# Sheet1.net
KiCad netlist of a schematic drawn in Altium Designer
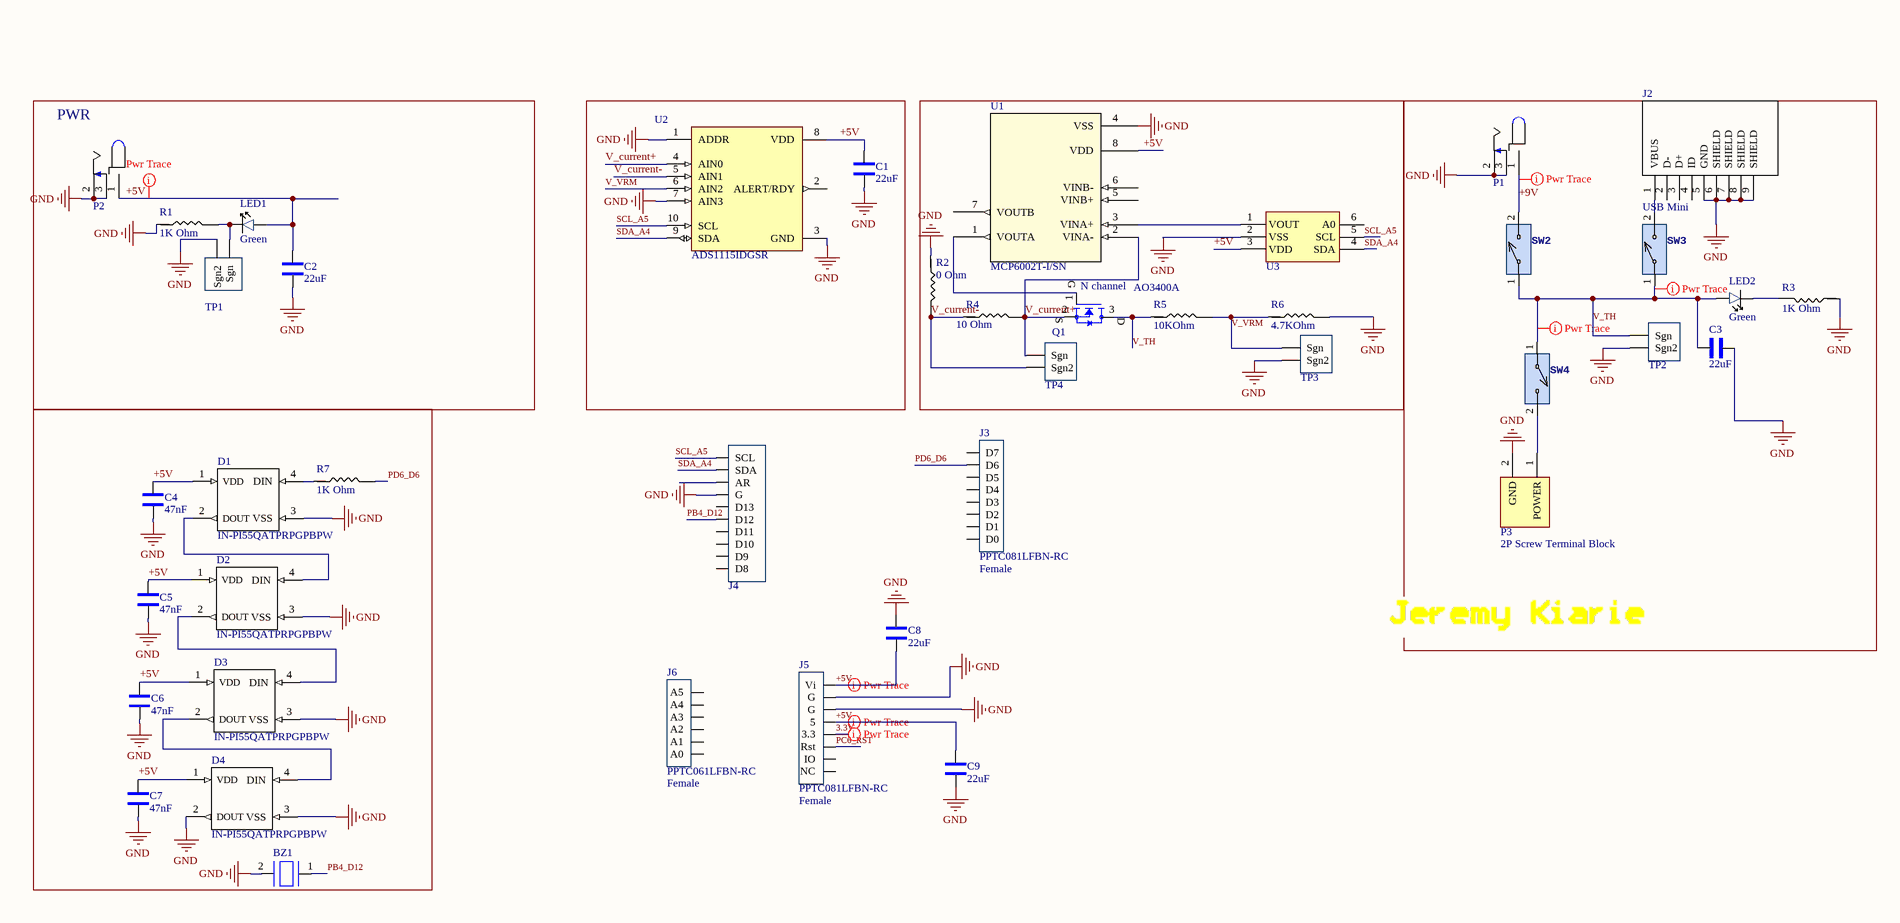
[diagram p0: Sheet1.SchDoc, left]
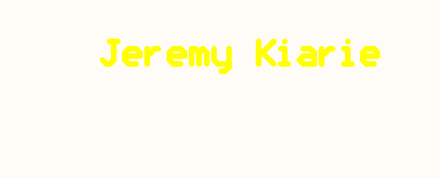
[diagram p1: Sheet1.SchDoc, right]

(export (version "E")
  (design (tool "Eeschema 10.0.6"))
  (components
    (comp (ref "BZ1")
      (value "AT-1224-TWT-5V-2-R")
      (footprint "BUZZER- TH")
      (libsource (lib "ECEN5730Lib_2023_05_DS") (part "BUZZER_1"))
    )
    (comp (ref "C1")
      (value "22uF")
      (footprint "1206_Passive_Capacitor")
      (description "22uF ±10% 25V X5R 1206 Multilayer Ceramic Capacitors MLCC - SMD/SMT RoHS")
      (fields (field (name "MFR PART #") "CL31A226KAHNNNE") (field (name "LCSC PART#") "C12891"))
      (libsource (lib "ECEN5730Lib_2023_05_DS") (part "C_22uF_1206"))
    )
    (comp (ref "C2")
      (value "22uF")
      (footprint "1206_Passive_Capacitor")
      (description "22uF ±10% 25V X5R 1206 Multilayer Ceramic Capacitors MLCC - SMD/SMT RoHS")
      (fields (field (name "MFR PART #") "CL31A226KAHNNNE") (field (name "LCSC PART#") "C12891"))
      (libsource (lib "ECEN5730Lib_2023_05_DS") (part "C_22uF_1206"))
    )
    (comp (ref "C3")
      (value "22uF")
      (footprint "1206_Passive_Capacitor")
      (description "22uF ±10% 25V X5R 1206 Multilayer Ceramic Capacitors MLCC - SMD/SMT RoHS")
      (fields (field (name "MFR PART #") "CL31A226KAHNNNE") (field (name "LCSC PART#") "C12891"))
      (libsource (lib "ECEN5730Lib_2023_05_DS") (part "C_22uF_1206"))
    )
    (comp (ref "C4")
      (value "47nF")
      (footprint "1206_Passive_Capacitor")
      (description "47nF ±5% 50V C0G 1206 Multilayer Ceramic Capacitors MLCC - SMD/SMT RoHS")
      (fields (field (name "LCSC PART#") "C21812") (field (name "MFR PART #") "GRM31M5C1H473JA01L"))
      (libsource (lib "ECEN5730Lib_2023_05_DS") (part "C_47nF_1206"))
    )
    (comp (ref "C5")
      (value "47nF")
      (footprint "1206_Passive_Capacitor")
      (description "47nF ±5% 50V C0G 1206 Multilayer Ceramic Capacitors MLCC - SMD/SMT RoHS")
      (fields (field (name "LCSC PART#") "C21812") (field (name "MFR PART #") "GRM31M5C1H473JA01L"))
      (libsource (lib "ECEN5730Lib_2023_05_DS") (part "C_47nF_1206"))
    )
    (comp (ref "C6")
      (value "47nF")
      (footprint "1206_Passive_Capacitor")
      (description "47nF ±5% 50V C0G 1206 Multilayer Ceramic Capacitors MLCC - SMD/SMT RoHS")
      (fields (field (name "LCSC PART#") "C21812") (field (name "MFR PART #") "GRM31M5C1H473JA01L"))
      (libsource (lib "ECEN5730Lib_2023_05_DS") (part "C_47nF_1206"))
    )
    (comp (ref "C7")
      (value "47nF")
      (footprint "1206_Passive_Capacitor")
      (description "47nF ±5% 50V C0G 1206 Multilayer Ceramic Capacitors MLCC - SMD/SMT RoHS")
      (fields (field (name "LCSC PART#") "C21812") (field (name "MFR PART #") "GRM31M5C1H473JA01L"))
      (libsource (lib "ECEN5730Lib_2023_05_DS") (part "C_47nF_1206"))
    )
    (comp (ref "C8")
      (value "22uF")
      (footprint "1206_Passive_Capacitor")
      (description "22uF ±10% 25V X5R 1206 Multilayer Ceramic Capacitors MLCC - SMD/SMT RoHS")
      (fields (field (name "MFR PART #") "CL31A226KAHNNNE") (field (name "LCSC PART#") "C12891"))
      (libsource (lib "ECEN5730Lib_2023_05_DS") (part "C_22uF_1206"))
    )
    (comp (ref "C9")
      (value "22uF")
      (footprint "1206_Passive_Capacitor")
      (description "22uF ±10% 25V X5R 1206 Multilayer Ceramic Capacitors MLCC - SMD/SMT RoHS")
      (fields (field (name "MFR PART #") "CL31A226KAHNNNE") (field (name "LCSC PART#") "C12891"))
      (libsource (lib "ECEN5730Lib_2023_05_DS") (part "C_22uF_1206"))
    )
    (comp (ref "D1")
      (value "IN-PI55QATPRPGPBPW")
      (footprint "SERIAL_LED - duplicate")
      (fields
        (field (name "LCSC PART#") "C2843785")
        (field (name "MFR PART #") "XL-5050RGBC-WS2812B")
        (field (name "MANUFACTURER") "XINGLIGHT")
      )
      (libsource (lib "ECEN5730Lib_2023_05_DS") (part "LED_Smart"))
    )
    (comp (ref "D2")
      (value "IN-PI55QATPRPGPBPW")
      (footprint "SERIAL_LED - duplicate")
      (fields
        (field (name "LCSC PART#") "C2843785")
        (field (name "MFR PART #") "XL-5050RGBC-WS2812B")
        (field (name "MANUFACTURER") "XINGLIGHT")
      )
      (libsource (lib "ECEN5730Lib_2023_05_DS") (part "LED_Smart"))
    )
    (comp (ref "D3")
      (value "IN-PI55QATPRPGPBPW")
      (footprint "SERIAL_LED - duplicate")
      (fields
        (field (name "LCSC PART#") "C2843785")
        (field (name "MFR PART #") "XL-5050RGBC-WS2812B")
        (field (name "MANUFACTURER") "XINGLIGHT")
      )
      (libsource (lib "ECEN5730Lib_2023_05_DS") (part "LED_Smart"))
    )
    (comp (ref "D4")
      (value "IN-PI55QATPRPGPBPW")
      (footprint "SERIAL_LED - duplicate")
      (fields
        (field (name "LCSC PART#") "C2843785")
        (field (name "MFR PART #") "XL-5050RGBC-WS2812B")
        (field (name "MANUFACTURER") "XINGLIGHT")
      )
      (libsource (lib "ECEN5730Lib_2023_05_DS") (part "LED_Smart"))
    )
    (comp (ref "J2")
      (value "USB Mini")
      (footprint "USB_MINI_B")
      (description "Through Hole USB Connectors RoHS")
      (fields (field (name "LCSC PART#") "C46398") (field (name "MFR PART #") "920-462A2021D10102"))
      (libsource (lib "ECEN5730Lib_2023_05_DS") (part "J_USB_B_Mini"))
    )
    (comp (ref "J3")
      (value "PPTC081LFBN-RC")
      (footprint "8_PIN_ARD-DIG_100MIL")
      (description "8 Position Header Connector 0.100\" (2.54mm) Through Hole Tin")
      (fields (field (name "LCSC PART#") "C27438") (field (name "ALTIUM_VALUE") "Female"))
      (libsource (lib "ECEN5730Lib_2023_05_DS") (part "JF_8_PIN_FEMA_ARD-Dig"))
    )
    (comp (ref "J4")
      (value "PPTC101LFBN-RC")
      (footprint "10_PIN_ARDUINO_100MIL")
      (description "10 Position Header Connector 0.100\" (2.54mm) Through Hole Tin")
      (fields (field (name "LCSC PART#") "C225507"))
      (libsource (lib "ECEN5730Lib_2023_05_DS") (part "JF_10_PIN_FEMA_ARDUINO"))
    )
    (comp (ref "J5")
      (value "PPTC081LFBN-RC")
      (footprint "8_PIN_ARD-PWR_100MIL")
      (description "8 Position Header Connector 0.100\" (2.54mm) Through Hole Tin")
      (fields (field (name "LCSC PART#") "C27438") (field (name "ALTIUM_VALUE") "Female"))
      (libsource (lib "ECEN5730Lib_2023_05_DS") (part "JF_8_PIN_FEMA_ARD-Pwr"))
    )
    (comp (ref "J6")
      (value "PPTC061LFBN-RC")
      (footprint "6_PIN_ARD-Analog_100mil")
      (description "6 Position Header Connector 0.100\" (2.54mm) Through Hole Tin")
      (fields (field (name "LCSC PART#") "C40877") (field (name "ALTIUM_VALUE") "Female"))
      (libsource (lib "ECEN5730Lib_2023_05_DS") (part "JF_6_PIN_FEMA_ARD-Anolog"))
    )
    (comp (ref "LED1")
      (value "Green")
      (footprint "LED_1206")
      (description "Green 513~528nm 1206 Light Emitting Diodes (LED) RoHS")
      (fields (field (name "MFR PART #") "SZYY1206G") (field (name "LCSC PART#") "C434439"))
      (libsource (lib "ECEN5730Lib_2023_05_DS") (part "LED_GREEN_1206"))
    )
    (comp (ref "LED2")
      (value "Green")
      (footprint "LED_1206")
      (description "Green 513~528nm 1206 Light Emitting Diodes (LED) RoHS")
      (fields (field (name "MFR PART #") "SZYY1206G") (field (name "LCSC PART#") "C434439"))
      (libsource (lib "ECEN5730Lib_2023_05_DS") (part "LED_GREEN_1206"))
    )
    (comp (ref "P1")
      (value "Power Jack")
      (footprint "Power_Jack")
      (description "Power Barrel Connector Jack 2.10mm ID (0.083\"), 5.50mm OD (0.217\") Through Hole, Right Angle")
      (fields (field (name "MFR PART #") "PJ-102A") (field (name "LCSC PART#") "C136744"))
      (libsource (lib "ECEN5730Lib_2023_05_DS") (part "P_Power Jack"))
    )
    (comp (ref "P2")
      (value "Power Jack")
      (footprint "Power_Jack")
      (description "Power Barrel Connector Jack 2.10mm ID (0.083\"), 5.50mm OD (0.217\") Through Hole, Right Angle")
      (fields (field (name "MFR PART #") "PJ-102A") (field (name "LCSC PART#") "C136744"))
      (libsource (lib "ECEN5730Lib_2023_05_DS") (part "P_Power Jack"))
    )
    (comp (ref "P3")
      (value "2P Screw Terminal Block")
      (footprint "P_Terminal block 3.5mm-pitch")
      (description "Green Straight pin 3.5mm  pitch; P=3.5mm  Screw terminal ROHS")
      (fields (field (name "MFR PART #") "KF350-3.5-2P") (field (name "MANUFACTURER") "Cixi Kefa Elec"))
      (libsource (lib "ECEN5730Lib_2023_05_DS") (part "P_Terminal block"))
    )
    (comp (ref "Q1")
      (value "AO3400A")
      (footprint "N-MOSFET")
      (description "MOSFET N Trench 30V 5.7A 1.5V @ 250uA 26.5 m? @ 5.7A,10V SOT-23-3L RoHS")
      (fields (field (name "LCSC PART#") "C20917") (field (name "ALTIUM_VALUE") "N channel"))
      (libsource (lib "ECEN5730Lib_2023_05_DS") (part "Q_Nch_MOSFET"))
    )
    (comp (ref "R1")
      (value "1K Ohm")
      (footprint "1206_Passive_Resitor")
      (description "CHIP RESISTOR - SURFACE MOUNT 1KOHMS ±1% 1/4W 1206 ROHS")
      (fields (field (name "MFR PART #") "RNCP1206FTD1K00CT") (field (name "LCSC PART#") "C4410"))
      (libsource (lib "ECEN5730Lib_2023_05_DS") (part "R_1K_1206"))
    )
    (comp (ref "R2")
      (value "0 Ohm")
      (footprint "1206_Passive_Resitor")
      (description "CHIP RESISTOR - SURFACE MOUNT 0OHMS ±1% 1/4W 1206 ROHS")
      (fields (field (name "MFR PART #") "1206W4F0000T5E") (field (name "LCSC PART#") "C17888"))
      (libsource (lib "ECEN5730Lib_2023_05_DS") (part "R_0Ohm_1206"))
    )
    (comp (ref "R3")
      (value "1K Ohm")
      (footprint "1206_Passive_Resitor")
      (description "CHIP RESISTOR - SURFACE MOUNT 1KOHMS ±1% 1/4W 1206 ROHS")
      (fields (field (name "MFR PART #") "RNCP1206FTD1K00CT") (field (name "LCSC PART#") "C4410"))
      (libsource (lib "ECEN5730Lib_2023_05_DS") (part "R_1K_1206"))
    )
    (comp (ref "R4")
      (value "10 Ohm")
      (footprint "1206_Passive_Resitor")
      (description "CHIP RESISTOR - SURFACE MOUNT 0.1OHMS ±1% 1/4W 1206 ROHS")
      (fields (field (name "MFR PART #") "1206W4F100JT5E") (field (name "LCSC PART#") "C17903"))
      (libsource (lib "ECEN5730Lib_2023_05_DS") (part "R_10Ohm_1206"))
    )
    (comp (ref "R5")
      (value "10KOhm")
      (footprint "1206_Passive_Resitor")
      (description "10 kOhms ±5% 0.25W, 1/4W Chip Resistor 1206 (3216 Metric) Automotive AEC-Q200 Thick Film")
      (fields (field (name "MFR PART #") "RMCF1206FT10K0") (field (name "LCSC PART#") "C17902"))
      (libsource (lib "ECEN5730Lib_2023_05_DS") (part "R_10KOhm_1206"))
    )
    (comp (ref "R6")
      (value "4.7KOhm")
      (footprint "1206_Passive_Resitor")
      (description "4.7kΩ ±1% 0.25W ±100ppm/℃ 1206 Chip Resistor - Surface Mount RoHS")
      (fields (field (name "LCSC PART#") "C17936") (field (name "MFR PART #") "1206W4F4701T5E"))
      (libsource (lib "ECEN5730Lib_2023_05_DS") (part "R_4.7k_1206"))
    )
    (comp (ref "R7")
      (value "1K Ohm")
      (footprint "1206_Passive_Resitor")
      (description "CHIP RESISTOR - SURFACE MOUNT 1KOHMS ±1% 1/4W 1206 ROHS")
      (fields (field (name "MFR PART #") "RNCP1206FTD1K00CT") (field (name "LCSC PART#") "C4410"))
      (libsource (lib "ECEN5730Lib_2023_05_DS") (part "R_1K_1206"))
    )
    (comp (ref "SW2")
      (value "SW_2Pin_100mil_Switch")
      (footprint "2Pin-Header-Conn")
      (description "2Pin Header")
      (fields (field (name "LCSC PART#") "C124375"))
      (libsource (lib "ECEN5730Lib_2023_05_DS") (part "SW_2Pin_100mil_Switch"))
    )
    (comp (ref "SW3")
      (value "SW_2Pin_100mil_Switch")
      (footprint "2Pin-Header-Conn")
      (description "2Pin Header")
      (fields (field (name "LCSC PART#") "C124375"))
      (libsource (lib "ECEN5730Lib_2023_05_DS") (part "SW_2Pin_100mil_Switch"))
    )
    (comp (ref "SW4")
      (value "SW_2Pin_100mil_Switch")
      (footprint "2Pin-Header-Conn")
      (description "2Pin Header")
      (fields (field (name "LCSC PART#") "C124375"))
      (libsource (lib "") (part "SW_2Pin_100mil_Switch_1"))
    )
    (comp (ref "TP1")
      (value "10x Probe TP")
      (footprint "TP_Diff_Probe")
      (description "Test Point 300 mil centers")
      (libsource (lib "") (part "TP_Diff_Probe_1"))
    )
    (comp (ref "TP2")
      (value "10x Probe TP")
      (footprint "TP_Diff_Probe")
      (description "Test Point 300 mil centers")
      (libsource (lib "ECEN5730Lib_2023_05_DS") (part "TP_Diff_Probe"))
    )
    (comp (ref "TP3")
      (value "10x Probe TP")
      (footprint "TP_Diff_Probe")
      (description "Test Point 300 mil centers")
      (libsource (lib "ECEN5730Lib_2023_05_DS") (part "TP_Diff_Probe"))
    )
    (comp (ref "TP4")
      (value "10x Probe TP")
      (footprint "TP_Diff_Probe")
      (description "Test Point 300 mil centers")
      (libsource (lib "ECEN5730Lib_2023_05_DS") (part "TP_Diff_Probe"))
    )
    (comp (ref "U1")
      (value "MCP6002T-I/SN")
      (footprint "SOIC127P600X175-8N")
      (description "0.6 V/us 2 1MHz 1.8V ~ 6V 100μA General Purpose SOIC-8_150mil  Operational Amplifier ROHS")
      (fields (field (name "MFR") "Microchip") (field (name "LCSC PART#") "C7377"))
      (libsource (lib "ECEN5730Lib_2023_05_DS") (part "U_MCP6002T-I/SN"))
    )
    (comp (ref "U2")
      (value "ADS1115IDGSR")
      (footprint "ADC_ADS1115IDGSR")
      (description "16-Bit ADC with Integrated MUX, PGA, Comparator, Oscillator, and Reference 10-VSSOP -40 to 125")
      (fields (field (name "LCSC PART#") "C37593"))
      (libsource (lib "ECEN5730Lib_2023_05_DS") (part "U_ADC_ADS1115IDGSR"))
    )
    (comp (ref "U3")
      (value "DAC IC")
      (footprint "MCP4725")
      (description "IC DAC 12BIT V-OUT SOT23-6")
      (fields (field (name "LCSC PART#") "C144198") (field (name "MFR PART #") "MCP4725A0T-E/CH"))
      (libsource (lib "ECEN5730Lib_2023_05_DS") (part "U_MCP4725A0T-E/CH"))
    )
  )
  (nets
    (net (code "1") (name "/+5V") (class "Default")
      (node (ref "C1") (pin "2") (pinfunction "2_2") (pintype "passive"))
      (node (ref "C2") (pin "2") (pinfunction "2_2") (pintype "passive"))
      (node (ref "C4") (pin "2") (pinfunction "2_2") (pintype "passive"))
      (node (ref "C5") (pin "2") (pinfunction "2_2") (pintype "passive"))
      (node (ref "C8") (pin "1") (pinfunction "1_1") (pintype "passive"))
      (node (ref "C9") (pin "1") (pinfunction "1_1") (pintype "passive"))
      (node (ref "D1") (pin "1") (pinfunction "VDD_1") (pintype "input"))
      (node (ref "D2") (pin "1") (pinfunction "VDD_1") (pintype "input"))
      (node (ref "J5") (pin "5") (pinfunction "5_5") (pintype "passive"))
      (node (ref "J5") (pin "8") (pinfunction "Vi_8") (pintype "passive"))
      (node (ref "LED1") (pin "1") (pinfunction "1_1") (pintype "passive"))
      (node (ref "P2") (pin "1") (pinfunction "1_1") (pintype "power_in"))
      (node (ref "U1") (pin "8") (pinfunction "VDD_8") (pintype "passive"))
      (node (ref "U2") (pin "8") (pinfunction "VDD_8") (pintype "power_in"))
      (node (ref "U3") (pin "3") (pinfunction "VDD_3") (pintype "passive"))
    )
    (net (code "2") (name "/+9V") (class "Default")
      (node (ref "P1") (pin "1") (pinfunction "1_1") (pintype "power_in"))
      (node (ref "SW2") (pin "2") (pinfunction "2_2") (pintype "passive"))
    )
    (net (code "3") (name "/3.3V") (class "Default")
      (node (ref "J5") (pin "4") (pinfunction "3.3_4") (pintype "passive"))
    )
    (net (code "5") (name "/PB4_D12") (class "Default")
      (node (ref "BZ1") (pin "1") (pinfunction "BZ1_1") (pintype "passive"))
      (node (ref "J4") (pin "6") (pinfunction "D12_6") (pintype "passive"))
    )
    (net (code "6") (name "/PC6_RST") (class "Default")
      (node (ref "J5") (pin "3") (pinfunction "Rst_3") (pintype "passive"))
    )
    (net (code "7") (name "/PD6_D6") (class "Default")
      (node (ref "J3") (pin "2") (pinfunction "D6_2") (pintype "passive"))
      (node (ref "R7") (pin "2") (pinfunction "2_2") (pintype "passive"))
    )
    (net (code "8") (name "/SCL_A5") (class "Default")
      (node (ref "J4") (pin "1") (pinfunction "SCL_1") (pintype "passive"))
      (node (ref "U2") (pin "10") (pinfunction "SCL_10") (pintype "input"))
      (node (ref "U3") (pin "5") (pinfunction "SCL_5") (pintype "passive"))
    )
    (net (code "9") (name "/SDA_A4") (class "Default")
      (node (ref "J4") (pin "2") (pinfunction "SDA_2") (pintype "passive"))
      (node (ref "U2") (pin "9") (pinfunction "SDA_9") (pintype "bidirectional"))
      (node (ref "U3") (pin "4") (pinfunction "SDA_4") (pintype "passive"))
    )
    (net (code "10") (name "/V_TH") (class "Default")
      (node (ref "C3") (pin "2") (pinfunction "2_2") (pintype "passive"))
      (node (ref "LED2") (pin "1") (pinfunction "1_1") (pintype "passive"))
      (node (ref "Q1") (pin "3") (pinfunction "D_3") (pintype "passive"))
      (node (ref "R5") (pin "1") (pinfunction "1_1") (pintype "passive"))
      (node (ref "SW2") (pin "1") (pinfunction "1_1") (pintype "passive"))
      (node (ref "SW3") (pin "1") (pinfunction "1_1") (pintype "passive"))
      (node (ref "SW4") (pin "1") (pinfunction "1_1") (pintype "passive"))
      (node (ref "TP2") (pin "1") (pinfunction "Sgn_1") (pintype "passive"))
    )
    (net (code "11") (name "/V_VRM") (class "Default")
      (node (ref "R5") (pin "2") (pinfunction "2_2") (pintype "passive"))
      (node (ref "R6") (pin "1") (pinfunction "1_1") (pintype "passive"))
      (node (ref "TP3") (pin "1") (pinfunction "Sgn_1") (pintype "passive"))
      (node (ref "U2") (pin "6") (pinfunction "AIN2_6") (pintype "input"))
    )
    (net (code "12") (name "/V_current+") (class "Default")
      (node (ref "Q1") (pin "2") (pinfunction "S_2") (pintype "passive"))
      (node (ref "R4") (pin "2") (pinfunction "2_2") (pintype "passive"))
      (node (ref "TP4") (pin "1") (pinfunction "Sgn_1") (pintype "passive"))
      (node (ref "U1") (pin "2") (pinfunction "VINA-_2") (pintype "input"))
      (node (ref "U2") (pin "4") (pinfunction "AIN0_4") (pintype "input"))
    )
    (net (code "13") (name "/V_current-") (class "Default")
      (node (ref "R2") (pin "2") (pinfunction "2_2") (pintype "passive"))
      (node (ref "R4") (pin "1") (pinfunction "1_1") (pintype "passive"))
      (node (ref "TP4") (pin "2") (pinfunction "Sgn2_2") (pintype "passive"))
      (node (ref "U2") (pin "5") (pinfunction "AIN1_5") (pintype "input"))
    )
    (net (code "14") (name "GND") (class "Default")
      (node (ref "BZ1") (pin "2") (pinfunction "BZ2_2") (pintype "passive"))
      (node (ref "C1") (pin "1") (pinfunction "1_1") (pintype "passive"))
      (node (ref "C2") (pin "1") (pinfunction "1_1") (pintype "passive"))
      (node (ref "C3") (pin "1") (pinfunction "1_1") (pintype "passive"))
      (node (ref "C4") (pin "1") (pinfunction "1_1") (pintype "passive"))
      (node (ref "C5") (pin "1") (pinfunction "1_1") (pintype "passive"))
      (node (ref "C6") (pin "1") (pinfunction "1_1") (pintype "passive"))
      (node (ref "C7") (pin "1") (pinfunction "1_1") (pintype "passive"))
      (node (ref "C8") (pin "2") (pinfunction "2_2") (pintype "passive"))
      (node (ref "C9") (pin "2") (pinfunction "2_2") (pintype "passive"))
      (node (ref "D1") (pin "3") (pinfunction "VSS_3") (pintype "input"))
      (node (ref "D2") (pin "3") (pinfunction "VSS_3") (pintype "input"))
      (node (ref "D3") (pin "3") (pinfunction "VSS_3") (pintype "input"))
      (node (ref "D4") (pin "2") (pinfunction "DOUT_2") (pintype "output"))
      (node (ref "D4") (pin "3") (pinfunction "VSS_3") (pintype "input"))
      (node (ref "J2") (pin "5") (pinfunction "GND_5") (pintype "passive"))
      (node (ref "J2") (pin "6") (pinfunction "SHIELD_6") (pintype "passive"))
      (node (ref "J2") (pin "7") (pinfunction "SHIELD_7") (pintype "passive"))
      (node (ref "J2") (pin "8") (pinfunction "SHIELD_8") (pintype "passive"))
      (node (ref "J2") (pin "9") (pinfunction "SHIELD_9") (pintype "passive"))
      (node (ref "J4") (pin "4") (pinfunction "G_4") (pintype "passive"))
      (node (ref "J5") (pin "6") (pinfunction "G_6") (pintype "passive"))
      (node (ref "J5") (pin "7") (pinfunction "G_7") (pintype "passive"))
      (node (ref "P1") (pin "2") (pinfunction "2_2") (pintype "power_in"))
      (node (ref "P1") (pin "3") (pinfunction "3_3") (pintype "power_in"))
      (node (ref "P2") (pin "2") (pinfunction "2_2") (pintype "power_in"))
      (node (ref "P2") (pin "3") (pinfunction "3_3") (pintype "power_in"))
      (node (ref "P3") (pin "2") (pinfunction "GND_2") (pintype "passive"))
      (node (ref "R1") (pin "1") (pinfunction "1_1") (pintype "passive"))
      (node (ref "R2") (pin "1") (pinfunction "1_1") (pintype "passive"))
      (node (ref "R3") (pin "1") (pinfunction "1_1") (pintype "passive"))
      (node (ref "R6") (pin "2") (pinfunction "2_2") (pintype "passive"))
      (node (ref "TP1") (pin "2") (pinfunction "Sgn2_2") (pintype "passive"))
      (node (ref "TP2") (pin "2") (pinfunction "Sgn2_2") (pintype "passive"))
      (node (ref "TP3") (pin "2") (pinfunction "Sgn2_2") (pintype "passive"))
      (node (ref "U1") (pin "4") (pinfunction "VSS_4") (pintype "passive"))
      (node (ref "U2") (pin "1") (pinfunction "ADDR_1") (pintype "passive"))
      (node (ref "U2") (pin "3") (pinfunction "GND_3") (pintype "power_in"))
      (node (ref "U2") (pin "7") (pinfunction "AIN3_7") (pintype "input"))
      (node (ref "U3") (pin "2") (pinfunction "VSS_2") (pintype "passive"))
    )
    (net (code "15") (name "Net-(D1-DIN)") (class "Default")
      (node (ref "D1") (pin "4") (pinfunction "DIN_4") (pintype "input"))
      (node (ref "R7") (pin "1") (pinfunction "1_1") (pintype "passive"))
    )
    (net (code "16") (name "Net-(D1-DOUT)") (class "Default")
      (node (ref "D1") (pin "2") (pinfunction "DOUT_2") (pintype "output"))
      (node (ref "D2") (pin "4") (pinfunction "DIN_4") (pintype "input"))
    )
    (net (code "17") (name "Net-(D2-DOUT)") (class "Default")
      (node (ref "D2") (pin "2") (pinfunction "DOUT_2") (pintype "output"))
      (node (ref "D3") (pin "4") (pinfunction "DIN_4") (pintype "input"))
    )
    (net (code "18") (name "Net-(D3-DOUT)") (class "Default")
      (node (ref "D3") (pin "2") (pinfunction "DOUT_2") (pintype "output"))
      (node (ref "D4") (pin "4") (pinfunction "DIN_4") (pintype "input"))
    )
    (net (code "19") (name "Net-(D3-VDD)") (class "Default")
      (node (ref "C6") (pin "2") (pinfunction "2_2") (pintype "passive"))
      (node (ref "D3") (pin "1") (pinfunction "VDD_1") (pintype "input"))
    )
    (net (code "20") (name "Net-(D4-VDD)") (class "Default")
      (node (ref "C7") (pin "2") (pinfunction "2_2") (pintype "passive"))
      (node (ref "D4") (pin "1") (pinfunction "VDD_1") (pintype "input"))
    )
    (net (code "21") (name "Net-(J2-VBUS)") (class "Default")
      (node (ref "J2") (pin "1") (pinfunction "VBUS_1") (pintype "passive"))
      (node (ref "SW3") (pin "2") (pinfunction "2_2") (pintype "passive"))
    )
    (net (code "22") (name "Net-(LED2-Pad2)") (class "Default")
      (node (ref "LED2") (pin "2") (pinfunction "2_2") (pintype "passive"))
      (node (ref "R3") (pin "2") (pinfunction "2_2") (pintype "passive"))
    )
    (net (code "23") (name "Net-(P3-POWER)") (class "Default")
      (node (ref "P3") (pin "1") (pinfunction "POWER_1") (pintype "passive"))
      (node (ref "SW4") (pin "2") (pinfunction "2_2") (pintype "passive"))
    )
    (net (code "24") (name "Net-(Q1-G)") (class "Default")
      (node (ref "Q1") (pin "1") (pinfunction "G_1") (pintype "passive"))
      (node (ref "U1") (pin "1") (pinfunction "VOUTA_1") (pintype "output"))
    )
    (net (code "25") (name "Net-(TP1-Sgn)") (class "Default")
      (node (ref "LED1") (pin "2") (pinfunction "2_2") (pintype "passive"))
      (node (ref "R1") (pin "2") (pinfunction "2_2") (pintype "passive"))
      (node (ref "TP1") (pin "1") (pinfunction "Sgn_1") (pintype "passive"))
    )
    (net (code "26") (name "Net-(U1-VINA+)") (class "Default")
      (node (ref "U1") (pin "3") (pinfunction "VINA+_3") (pintype "input"))
      (node (ref "U3") (pin "1") (pinfunction "VOUT_1") (pintype "passive"))
    )
    (net (code "27") (name "unconnected-(J2-D+-Pad3)") (class "Default")
      (node (ref "J2") (pin "3") (pinfunction "D+_3") (pintype "passive"))
    )
    (net (code "28") (name "unconnected-(J2-D--Pad2)") (class "Default")
      (node (ref "J2") (pin "2") (pinfunction "D-_2") (pintype "passive"))
    )
    (net (code "29") (name "unconnected-(J2-ID-Pad4)") (class "Default")
      (node (ref "J2") (pin "4") (pinfunction "ID_4") (pintype "passive"))
    )
    (net (code "30") (name "unconnected-(J3-D0-Pad8)") (class "Default")
      (node (ref "J3") (pin "8") (pinfunction "D0_8") (pintype "passive"))
    )
    (net (code "31") (name "unconnected-(J3-D1-Pad7)") (class "Default")
      (node (ref "J3") (pin "7") (pinfunction "D1_7") (pintype "passive"))
    )
    (net (code "32") (name "unconnected-(J3-D2-Pad6)") (class "Default")
      (node (ref "J3") (pin "6") (pinfunction "D2_6") (pintype "passive"))
    )
    (net (code "33") (name "unconnected-(J3-D3-Pad5)") (class "Default")
      (node (ref "J3") (pin "5") (pinfunction "D3_5") (pintype "passive"))
    )
    (net (code "34") (name "unconnected-(J3-D4-Pad4)") (class "Default")
      (node (ref "J3") (pin "4") (pinfunction "D4_4") (pintype "passive"))
    )
    (net (code "35") (name "unconnected-(J3-D5-Pad3)") (class "Default")
      (node (ref "J3") (pin "3") (pinfunction "D5_3") (pintype "passive"))
    )
    (net (code "36") (name "unconnected-(J3-D7-Pad1)") (class "Default")
      (node (ref "J3") (pin "1") (pinfunction "D7_1") (pintype "passive"))
    )
    (net (code "37") (name "unconnected-(J4-AR-Pad3)") (class "Default")
      (node (ref "J4") (pin "3") (pinfunction "AR_3") (pintype "passive"))
    )
    (net (code "38") (name "unconnected-(J4-D8-Pad10)") (class "Default")
      (node (ref "J4") (pin "10") (pinfunction "D8_10") (pintype "passive"))
    )
    (net (code "39") (name "unconnected-(J4-D9-Pad9)") (class "Default")
      (node (ref "J4") (pin "9") (pinfunction "D9_9") (pintype "passive"))
    )
    (net (code "40") (name "unconnected-(J4-D10-Pad8)") (class "Default")
      (node (ref "J4") (pin "8") (pinfunction "D10_8") (pintype "passive"))
    )
    (net (code "41") (name "unconnected-(J4-D11-Pad7)") (class "Default")
      (node (ref "J4") (pin "7") (pinfunction "D11_7") (pintype "passive"))
    )
    (net (code "42") (name "unconnected-(J4-D13-Pad5)") (class "Default")
      (node (ref "J4") (pin "5") (pinfunction "D13_5") (pintype "passive"))
    )
    (net (code "43") (name "unconnected-(J5-IO-Pad2)") (class "Default")
      (node (ref "J5") (pin "2") (pinfunction "IO_2") (pintype "passive"))
    )
    (net (code "44") (name "unconnected-(J5-NC-Pad1)") (class "Default")
      (node (ref "J5") (pin "1") (pinfunction "NC_1") (pintype "passive"))
    )
    (net (code "45") (name "unconnected-(J6-A0-Pad1)") (class "Default")
      (node (ref "J6") (pin "1") (pinfunction "A0_1") (pintype "passive"))
    )
    (net (code "46") (name "unconnected-(J6-A1-Pad2)") (class "Default")
      (node (ref "J6") (pin "2") (pinfunction "A1_2") (pintype "passive"))
    )
    (net (code "47") (name "unconnected-(J6-A2-Pad3)") (class "Default")
      (node (ref "J6") (pin "3") (pinfunction "A2_3") (pintype "passive"))
    )
    (net (code "48") (name "unconnected-(J6-A3-Pad4)") (class "Default")
      (node (ref "J6") (pin "4") (pinfunction "A3_4") (pintype "passive"))
    )
    (net (code "49") (name "unconnected-(J6-A4-Pad5)") (class "Default")
      (node (ref "J6") (pin "5") (pinfunction "A4_5") (pintype "passive"))
    )
    (net (code "50") (name "unconnected-(J6-A5-Pad6)") (class "Default")
      (node (ref "J6") (pin "6") (pinfunction "A5_6") (pintype "passive"))
    )
    (net (code "51") (name "unconnected-(U1-VINB+-Pad5)") (class "Default")
      (node (ref "U1") (pin "5") (pinfunction "VINB+_5") (pintype "input"))
    )
    (net (code "52") (name "unconnected-(U1-VINB--Pad6)") (class "Default")
      (node (ref "U1") (pin "6") (pinfunction "VINB-_6") (pintype "input"))
    )
    (net (code "53") (name "unconnected-(U1-VOUTB-Pad7)") (class "Default")
      (node (ref "U1") (pin "7") (pinfunction "VOUTB_7") (pintype "output"))
    )
    (net (code "54") (name "unconnected-(U2-ALERT{slash}RDY-Pad2)") (class "Default")
      (node (ref "U2") (pin "2") (pinfunction "ALERT/RDY_2") (pintype "output"))
    )
    (net (code "55") (name "unconnected-(U3-A0-Pad6)") (class "Default")
      (node (ref "U3") (pin "6") (pinfunction "A0_6") (pintype "passive"))
    )
  )
)
